# SmartPiezo.net
KiCad netlist of a schematic drawn in EAGLE
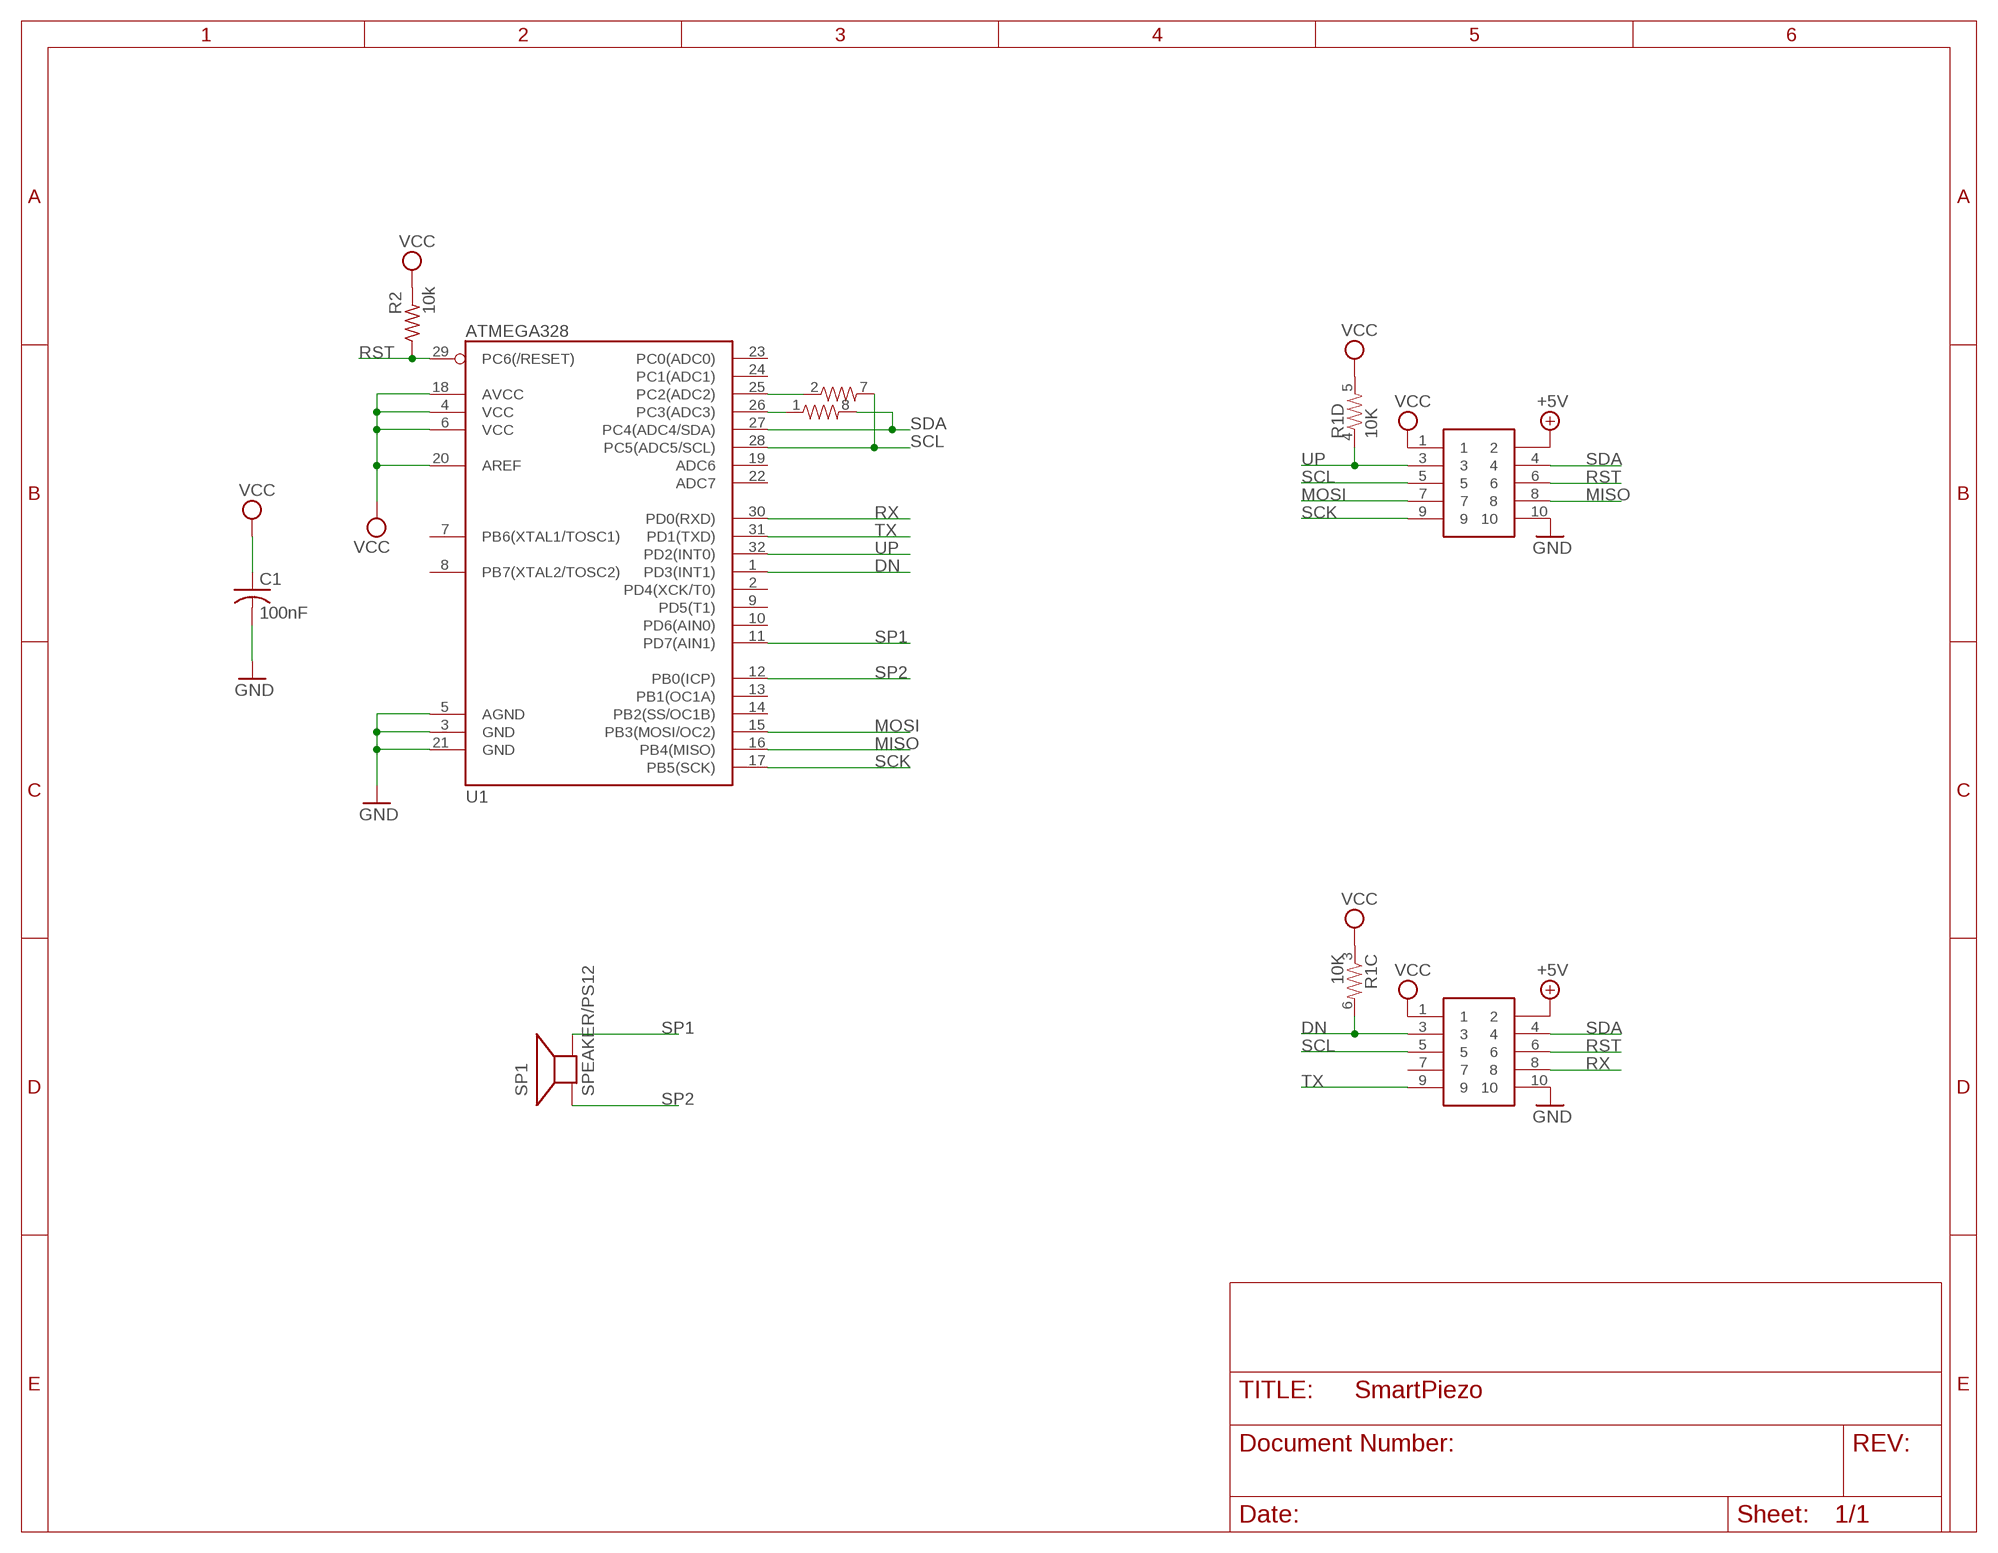
[diagram p0: schematic, sheet 1]

(export (version "E")
  (design (tool "Eeschema 10.0.6"))
  (components
    (comp (ref "*")
      (value "SHF105SM")
      (footprint "eagle-import:SHF105DSM")
      (libsource (lib "eagle-import") (part "SHF105SM"))
    )
    (comp (ref "C1")
      (value "100nF")
      (footprint "eagle-import:C0603K")
      (libsource (lib "eagle-import") (part "C-USC0603K"))
    )
    (comp (ref "R1")
      (value "10K")
      (footprint "eagle-import:0603-ARV")
      (libsource (lib "eagle-import") (part "RESISTOR-ARRAY0603-ARV"))
    )
    (comp (ref "R2")
      (value "10k")
      (footprint "eagle-import:R0603")
      (libsource (lib "eagle-import") (part "R-US_R0603"))
    )
    (comp (ref "SP1")
      (value "SPEAKER/PS12")
      (footprint "eagle-import:PS12")
      (libsource (lib "eagle-import") (part "SPEAKER/PS12"))
    )
    (comp (ref "U1")
      (value "ATMEGA328")
      (footprint "eagle-import:TQFP32-08")
      (libsource (lib "eagle-import") (part "ATMEGA168"))
    )
    (comp (ref "XY")
      (value "SHF105SM")
      (footprint "eagle-import:SHF105DSM")
      (libsource (lib "eagle-import") (part "SHF105SM"))
    )
  )
  (nets
    (net (code "1") (name "+5V") (class "Default")
      (node (ref "*") (pin "2") (pinfunction "2_2") (pintype "passive"))
      (node (ref "XY") (pin "2") (pinfunction "2_2") (pintype "passive"))
    )
    (net (code "2") (name "/DN") (class "Default")
      (node (ref "*") (pin "3") (pinfunction "3_3") (pintype "passive"))
      (node (ref "R1") (pin "6") (pinfunction "2_6") (pintype "passive"))
      (node (ref "U1") (pin "1") (pinfunction "PD3(INT1)_1") (pintype "bidirectional"))
    )
    (net (code "3") (name "/MISO") (class "Default")
      (node (ref "U1") (pin "16") (pinfunction "PB4(MISO)_16") (pintype "bidirectional"))
      (node (ref "XY") (pin "8") (pinfunction "8_8") (pintype "passive"))
    )
    (net (code "4") (name "/MOSI") (class "Default")
      (node (ref "U1") (pin "15") (pinfunction "PB3(MOSI/OC2)_15") (pintype "bidirectional"))
      (node (ref "XY") (pin "7") (pinfunction "7_7") (pintype "passive"))
    )
    (net (code "5") (name "/RST") (class "Default")
      (node (ref "*") (pin "6") (pinfunction "6_6") (pintype "passive"))
      (node (ref "R2") (pin "1") (pinfunction "1_1") (pintype "passive"))
      (node (ref "U1") (pin "29") (pinfunction "PC6(/RESET)_29") (pintype "bidirectional"))
      (node (ref "XY") (pin "6") (pinfunction "6_6") (pintype "passive"))
    )
    (net (code "6") (name "/RX") (class "Default")
      (node (ref "*") (pin "8") (pinfunction "8_8") (pintype "passive"))
      (node (ref "U1") (pin "30") (pinfunction "PD0(RXD)_30") (pintype "bidirectional"))
    )
    (net (code "7") (name "/SCK") (class "Default")
      (node (ref "U1") (pin "17") (pinfunction "PB5(SCK)_17") (pintype "bidirectional"))
      (node (ref "XY") (pin "9") (pinfunction "9_9") (pintype "passive"))
    )
    (net (code "8") (name "/SCL") (class "Default")
      (node (ref "*") (pin "5") (pinfunction "5_5") (pintype "passive"))
      (node (ref "R1") (pin "7") (pinfunction "2_7") (pintype "passive"))
      (node (ref "U1") (pin "28") (pinfunction "PC5(ADC5/SCL)_28") (pintype "bidirectional"))
      (node (ref "XY") (pin "5") (pinfunction "5_5") (pintype "passive"))
    )
    (net (code "9") (name "/SDA") (class "Default")
      (node (ref "*") (pin "4") (pinfunction "4_4") (pintype "passive"))
      (node (ref "R1") (pin "8") (pinfunction "2_8") (pintype "passive"))
      (node (ref "U1") (pin "27") (pinfunction "PC4(ADC4/SDA)_27") (pintype "bidirectional"))
      (node (ref "XY") (pin "4") (pinfunction "4_4") (pintype "passive"))
    )
    (net (code "10") (name "/SP1") (class "Default")
      (node (ref "SP1") (pin "P$2") (pinfunction "-_P$2") (pintype "passive"))
      (node (ref "U1") (pin "11") (pinfunction "PD7(AIN1)_11") (pintype "bidirectional"))
    )
    (net (code "11") (name "/SP2") (class "Default")
      (node (ref "SP1") (pin "P$1") (pinfunction "+_P$1") (pintype "passive"))
      (node (ref "U1") (pin "12") (pinfunction "PB0(ICP)_12") (pintype "bidirectional"))
    )
    (net (code "12") (name "/TX") (class "Default")
      (node (ref "*") (pin "9") (pinfunction "9_9") (pintype "passive"))
      (node (ref "U1") (pin "31") (pinfunction "PD1(TXD)_31") (pintype "bidirectional"))
    )
    (net (code "13") (name "/UP") (class "Default")
      (node (ref "R1") (pin "4") (pinfunction "1_4") (pintype "passive"))
      (node (ref "U1") (pin "32") (pinfunction "PD2(INT0)_32") (pintype "bidirectional"))
      (node (ref "XY") (pin "3") (pinfunction "3_3") (pintype "passive"))
    )
    (net (code "14") (name "GND") (class "Default")
      (node (ref "*") (pin "10") (pinfunction "10_10") (pintype "passive"))
      (node (ref "C1") (pin "2") (pinfunction "2_2") (pintype "passive"))
      (node (ref "U1") (pin "21") (pinfunction "GND_21") (pintype "bidirectional"))
      (node (ref "U1") (pin "3") (pinfunction "GND_3") (pintype "bidirectional"))
      (node (ref "U1") (pin "5") (pinfunction "AGND_5") (pintype "bidirectional"))
      (node (ref "XY") (pin "10") (pinfunction "10_10") (pintype "passive"))
    )
    (net (code "15") (name "Net-(R1B-1)") (class "Default")
      (node (ref "R1") (pin "2") (pinfunction "1_2") (pintype "passive"))
      (node (ref "U1") (pin "25") (pinfunction "PC2(ADC2)_25") (pintype "bidirectional"))
    )
    (net (code "16") (name "Net-(U1-PC3(ADC3))") (class "Default")
      (node (ref "R1") (pin "1") (pinfunction "1_1") (pintype "passive"))
      (node (ref "U1") (pin "26") (pinfunction "PC3(ADC3)_26") (pintype "bidirectional"))
    )
    (net (code "17") (name "VCC") (class "Default")
      (node (ref "*") (pin "1") (pinfunction "1_1") (pintype "passive"))
      (node (ref "C1") (pin "1") (pinfunction "1_1") (pintype "passive"))
      (node (ref "R1") (pin "3") (pinfunction "1_3") (pintype "passive"))
      (node (ref "R1") (pin "5") (pinfunction "2_5") (pintype "passive"))
      (node (ref "R2") (pin "2") (pinfunction "2_2") (pintype "passive"))
      (node (ref "U1") (pin "18") (pinfunction "AVCC_18") (pintype "bidirectional"))
      (node (ref "U1") (pin "20") (pinfunction "AREF_20") (pintype "bidirectional"))
      (node (ref "U1") (pin "4") (pinfunction "VCC_4") (pintype "bidirectional"))
      (node (ref "U1") (pin "6") (pinfunction "VCC_6") (pintype "bidirectional"))
      (node (ref "XY") (pin "1") (pinfunction "1_1") (pintype "passive"))
    )
    (net (code "18") (name "unconnected-(*-Pad7)") (class "Default")
      (node (ref "*") (pin "7") (pinfunction "7_7") (pintype "passive"))
    )
    (net (code "19") (name "unconnected-(U1-ADC6-Pad19)") (class "Default")
      (node (ref "U1") (pin "19") (pinfunction "ADC6_19") (pintype "bidirectional"))
    )
    (net (code "20") (name "unconnected-(U1-ADC7-Pad22)") (class "Default")
      (node (ref "U1") (pin "22") (pinfunction "ADC7_22") (pintype "bidirectional"))
    )
    (net (code "21") (name "unconnected-(U1-PB1(OC1A)-Pad13)") (class "Default")
      (node (ref "U1") (pin "13") (pinfunction "PB1(OC1A)_13") (pintype "bidirectional"))
    )
    (net (code "22") (name "unconnected-(U1-PB2(SS{slash}OC1B)-Pad14)") (class "Default")
      (node (ref "U1") (pin "14") (pinfunction "PB2(SS/OC1B)_14") (pintype "bidirectional"))
    )
    (net (code "23") (name "unconnected-(U1-PB6(XTAL1{slash}TOSC1)-Pad7)") (class "Default")
      (node (ref "U1") (pin "7") (pinfunction "PB6(XTAL1/TOSC1)_7") (pintype "bidirectional"))
    )
    (net (code "24") (name "unconnected-(U1-PB7(XTAL2{slash}TOSC2)-Pad8)") (class "Default")
      (node (ref "U1") (pin "8") (pinfunction "PB7(XTAL2/TOSC2)_8") (pintype "bidirectional"))
    )
    (net (code "25") (name "unconnected-(U1-PC0(ADC0)-Pad23)") (class "Default")
      (node (ref "U1") (pin "23") (pinfunction "PC0(ADC0)_23") (pintype "bidirectional"))
    )
    (net (code "26") (name "unconnected-(U1-PC1(ADC1)-Pad24)") (class "Default")
      (node (ref "U1") (pin "24") (pinfunction "PC1(ADC1)_24") (pintype "bidirectional"))
    )
    (net (code "27") (name "unconnected-(U1-PD4(XCK{slash}T0)-Pad2)") (class "Default")
      (node (ref "U1") (pin "2") (pinfunction "PD4(XCK/T0)_2") (pintype "bidirectional"))
    )
    (net (code "28") (name "unconnected-(U1-PD5(T1)-Pad9)") (class "Default")
      (node (ref "U1") (pin "9") (pinfunction "PD5(T1)_9") (pintype "bidirectional"))
    )
    (net (code "29") (name "unconnected-(U1-PD6(AIN0)-Pad10)") (class "Default")
      (node (ref "U1") (pin "10") (pinfunction "PD6(AIN0)_10") (pintype "bidirectional"))
    )
  )
)
